# RelayBoard.net
KiCad netlist of a schematic drawn in Altium Designer
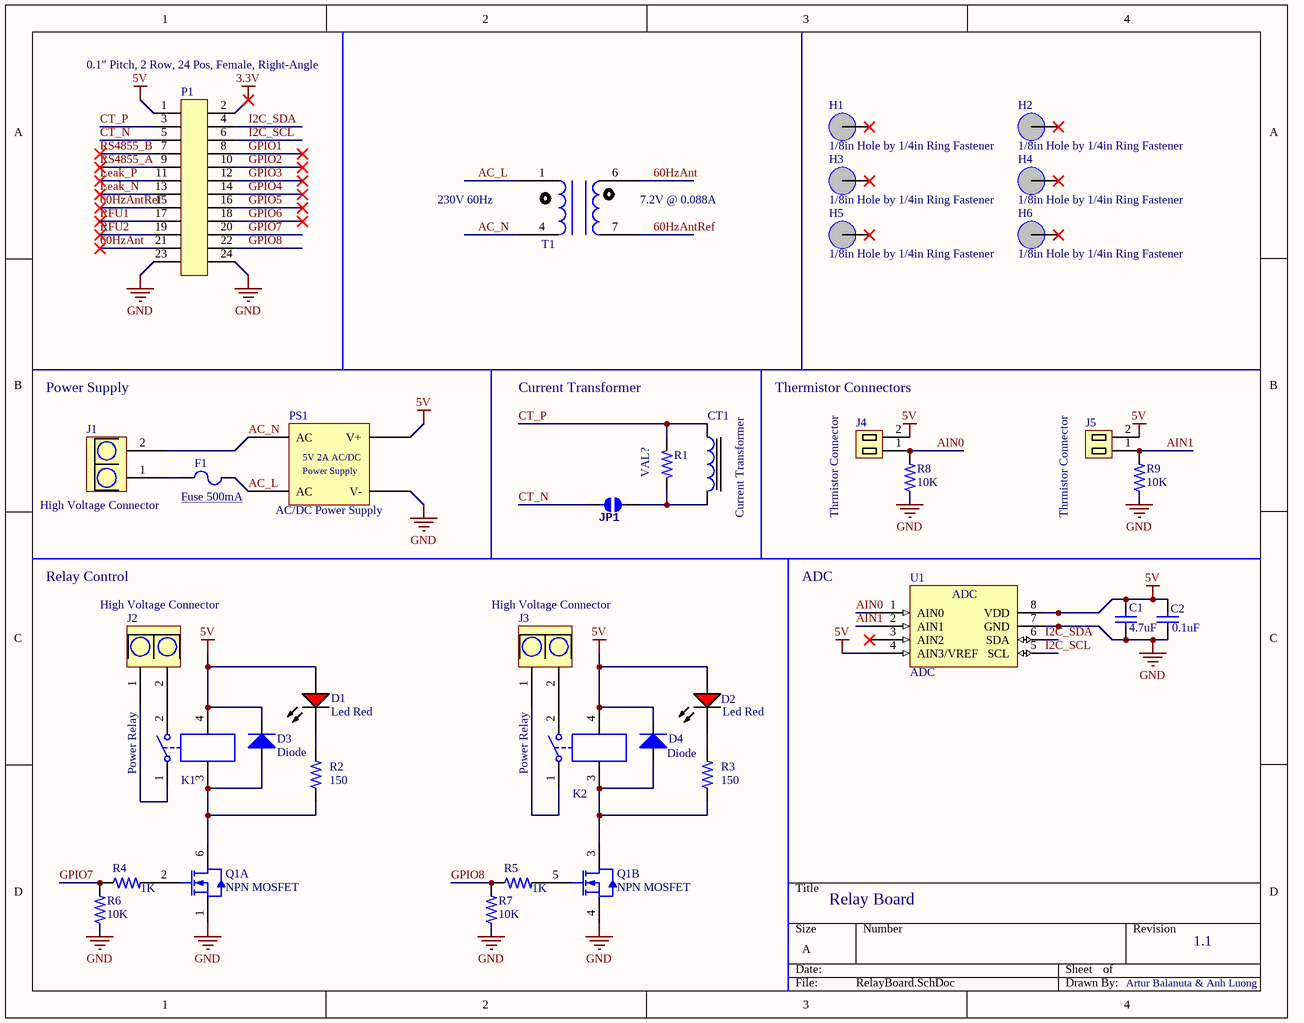
[diagram p0: RelayBoard.SchDoc]

(export (version "E")
  (design (tool "Eeschema 10.0.6"))
  (components
    (comp (ref "C1")
      (value "4.7uF")
      (footprint "CAPC1608X09L - CAP0603")
      (description "SMT 0603 Ceramic Capacitor")
      (fields (field (name "TOLERANCE") "10%") (field (name "VOLTAGE") "6.3V"))
      (libsource (lib "Passives") (part "CAP0603 4.7uF 10% 6.3V X7R"))
    )
    (comp (ref "C2")
      (value "0.1uF")
      (footprint "CAPC1608X09L - CAP0603")
      (description "SMT 0603 Ceramic Capacitor")
      (fields (field (name "TOLERANCE") "10%") (field (name "VOLTAGE") "25V"))
      (libsource (lib "Passives") (part "CAP0603 0.1uF 10% 25V X7R"))
    )
    (comp (ref "CT1")
      (value "Current Transformer")
      (footprint "CT-CR8348")
      (description "TRANSF CURRENT .27\" OPENING PCB 50A")
      (libsource (lib "Passives") (part "CT CR8348-2000"))
    )
    (comp (ref "D1")
      (value "Led Red")
      (footprint "LED-0603 .7MM TALL")
      (description "LED RED CLEAR 0603 SMD 250 mcd")
      (libsource (lib "Passives") (part "LED0603 RED 20mA 250mcd"))
    )
    (comp (ref "D2")
      (value "Led Red")
      (footprint "LED-0603 .7MM TALL")
      (description "LED RED CLEAR 0603 SMD 250 mcd")
      (libsource (lib "Passives") (part "LED0603 RED 20mA 250mcd"))
    )
    (comp (ref "D3")
      (value "Diode")
      (footprint "SOD-80  MiniMELF")
      (description "DIODE GEN 50V 600MA MINI MELF")
      (libsource (lib "Passives") (part "Diode LL4150GS18"))
    )
    (comp (ref "D4")
      (value "Diode")
      (footprint "SOD-80  MiniMELF")
      (description "DIODE GEN 50V 600MA MINI MELF")
      (libsource (lib "Passives") (part "Diode LL4150GS18"))
    )
    (comp (ref "F1")
      (value "Fuse 500mA")
      (footprint "FUSE M10742X40L Schurter UMK 250 Series")
      (description "FUSE UMK 250 FUSE WITH HOLDER 500MA F")
      (libsource (lib "Passives") (part "FUSE-Schurter-3404.2463.22"))
    )
    (comp (ref "H1")
      (value "1/8in Hole by 1/4in Ring Fastener")
      (footprint "1/8in Fastener Hole")
      (libsource (lib "Misc") (part "1/8in by 1/4in Fastner Hole"))
    )
    (comp (ref "H2")
      (value "1/8in Hole by 1/4in Ring Fastener")
      (footprint "1/8in Fastener Hole")
      (libsource (lib "Misc") (part "1/8in by 1/4in Fastner Hole"))
    )
    (comp (ref "H3")
      (value "1/8in Hole by 1/4in Ring Fastener")
      (footprint "1/8in Fastener Hole")
      (libsource (lib "Misc") (part "1/8in by 1/4in Fastner Hole"))
    )
    (comp (ref "H4")
      (value "1/8in Hole by 1/4in Ring Fastener")
      (footprint "1/8in Fastener Hole")
      (libsource (lib "Misc") (part "1/8in by 1/4in Fastner Hole"))
    )
    (comp (ref "H5")
      (value "1/8in Hole by 1/4in Ring Fastener")
      (footprint "1/8in Fastener Hole")
      (libsource (lib "Misc") (part "1/8in by 1/4in Fastner Hole"))
    )
    (comp (ref "H6")
      (value "1/8in Hole by 1/4in Ring Fastener")
      (footprint "1/8in Fastener Hole")
      (libsource (lib "Misc") (part "1/8in by 1/4in Fastner Hole"))
    )
    (comp (ref "J1")
      (value "High Voltage Connector")
      (footprint "2POS Barrier Block Terminal")
      (description "MOLEX  0386608802")
      (libsource (lib "Connectors") (part "2POS CONN BARRIER STRIP 2CIRC 0.5{dblquote} 45A 600V"))
    )
    (comp (ref "J2")
      (value "High Voltage Connector")
      (footprint "2POS Barrier Block Terminal")
      (description "MOLEX  0386608802")
      (libsource (lib "") (part "2POS CONN BARRIER STRIP 2CIRC 0.5{dblquote} 45A 600V_1"))
    )
    (comp (ref "J3")
      (value "High Voltage Connector")
      (footprint "2POS Barrier Block Terminal")
      (description "MOLEX  0386608802")
      (libsource (lib "") (part "2POS CONN BARRIER STRIP 2CIRC 0.5{dblquote} 45A 600V_1"))
    )
    (comp (ref "J4")
      (value "Thrmistor Connector")
      (footprint "2POS JST B02P-VL")
      (description "JST B02P-VL CONN HEADER 2POS VL SERIES TIN")
      (libsource (lib "Connectors") (part "2POS Thermistor Connector B02P-VL"))
    )
    (comp (ref "J5")
      (value "Thrmistor Connector")
      (footprint "2POS JST B02P-VL")
      (description "JST B02P-VL CONN HEADER 2POS VL SERIES TIN")
      (libsource (lib "Connectors") (part "2POS Thermistor Connector B02P-VL"))
    )
    (comp (ref "JP1")
      (value "JUMPER-PAD-2-NO")
      (footprint "PAD-JUMPER-2-NO_NO_SILK")
      (libsource (lib "Passives") (part "JUMPER-PAD-2-NO"))
    )
    (comp (ref "K1")
      (value "Power Relay")
      (footprint "T9AS1D12-5")
      (description "Single-Pole Single-Throw Relay")
      (fields (field (name "PART NUMBER") "T9AS1D12-5"))
      (libsource (lib "Relays") (part "T9AS1D12-5"))
    )
    (comp (ref "K2")
      (value "Power Relay")
      (footprint "T9AS1D12-5")
      (description "Single-Pole Single-Throw Relay")
      (fields (field (name "PART NUMBER") "T9AS1D12-5"))
      (libsource (lib "Relays") (part "T9AS1D12-5"))
    )
    (comp (ref "P1")
      (value "0.1\" Pitch, 2 Row, 24 Pos, Female, Right-Angle")
      (footprint "0.1 inch 2 row 24 pos female right-angle header Sullins")
      (description "Sullins 0.1\" 2 row 24 position female right-angle header")
      (libsource (lib "Connectors") (part "0.1{dblquote} 2 row 24 position female right-angle header sullins"))
    )
    (comp (ref "PS1")
      (value "AC/DC Power Supply")
      (footprint "IRM-10-5")
      (description "AC/DC Power Modules 5V 2A 10W 85-264Vin Encap PS")
      (libsource (lib "Power") (part "IRM-10-5"))
    )
    (comp (ref "Q1")
      (value "NPN MOSFET")
      (footprint "SC-70-6  (SOT-363)")
      (description "2N-CH NPN MOSFET 20V 1.3A SOT-363")
      (libsource (lib "Actives") (part "SI1922EDH-T1-GE3CT"))
    )
    (comp (ref "R1")
      (value "VAL?")
      (footprint "RESC1608X06L - RES0603")
      (description "SMT 0603 Ceramic Resistor")
      (libsource (lib "Passives") (part "RES0603"))
    )
    (comp (ref "R2")
      (value "150")
      (footprint "RESC1608X06L - RES0603")
      (description "SMT 0603 Ceramic Resistor")
      (libsource (lib "Passives") (part "RES0603 150 1% 1/10W_1"))
    )
    (comp (ref "R3")
      (value "150")
      (footprint "RESC1608X06L - RES0603")
      (description "SMT 0603 Ceramic Resistor")
      (libsource (lib "Passives") (part "RES0603 150 1% 1/10W_1"))
    )
    (comp (ref "R4")
      (value "1K")
      (footprint "RESC1608X06L - RES0603")
      (description "SMT 0603 Ceramic Resistor")
      (fields (field (name "POWER") "1/10W") (field (name "TOLERANCE") "1%"))
      (libsource (lib "Passives") (part "RES0603 1K 1% 1/10W"))
    )
    (comp (ref "R5")
      (value "1K")
      (footprint "RESC1608X06L - RES0603")
      (description "SMT 0603 Ceramic Resistor")
      (fields (field (name "POWER") "1/10W") (field (name "TOLERANCE") "1%"))
      (libsource (lib "Passives") (part "RES0603 1K 1% 1/10W"))
    )
    (comp (ref "R6")
      (value "10K")
      (footprint "RESC1608X06L - RES0603")
      (description "SMT 0603 Ceramic Resistor")
      (fields (field (name "POWER") "1/10W") (field (name "TOLERANCE") "1%"))
      (libsource (lib "Passives") (part "RES0603 10K 1% 1/10W"))
    )
    (comp (ref "R7")
      (value "10K")
      (footprint "RESC1608X06L - RES0603")
      (description "SMT 0603 Ceramic Resistor")
      (fields (field (name "POWER") "1/10W") (field (name "TOLERANCE") "1%"))
      (libsource (lib "Passives") (part "RES0603 10K 1% 1/10W"))
    )
    (comp (ref "R8")
      (value "10K")
      (footprint "RESC1608X06L - RES0603")
      (description "SMT 0603 Ceramic Resistor")
      (fields (field (name "POWER") "1/10W") (field (name "TOLERANCE") "1%"))
      (libsource (lib "Passives") (part "RES0603 10K 1% 1/10W"))
    )
    (comp (ref "R9")
      (value "10K")
      (footprint "RESC1608X06L - RES0603")
      (description "SMT 0603 Ceramic Resistor")
      (fields (field (name "POWER") "1/10W") (field (name "TOLERANCE") "1%"))
      (libsource (lib "Passives") (part "RES0603 10K 1% 1/10W"))
    )
    (comp (ref "T1")
      (value "SPK00304")
      (footprint "SPK003")
      (description "Standard PCB-Transformers ¦ SPK-003 ¦ POWER 0.35 VA")
      (libsource (lib "Power") (part "SPK00304"))
    )
    (comp (ref "U1")
      (value "ADC")
      (footprint "8L uMAX/uSOP TSOP65P490X110-8L")
      (description "IC ADC I2C/SRL 12BIT 4CH 8UMAX")
      (libsource (lib "Actives") (part "MAX11612EUA+"))
    )
  )
  (nets
    (net (code "1") (name "/60HzAnt") (class "Default")
      (node (ref "P1") (pin "21") (pintype "passive"))
      (node (ref "T1") (pin "6") (pinfunction "6_6") (pintype "passive"))
    )
    (net (code "2") (name "/60HzAntRef") (class "Default")
      (node (ref "P1") (pin "15") (pintype "passive"))
      (node (ref "T1") (pin "7") (pinfunction "7_7") (pintype "passive"))
    )
    (net (code "3") (name "/AC_L") (class "Default")
      (node (ref "F1") (pin "2") (pinfunction "2_2") (pintype "passive"))
      (node (ref "PS1") (pin "AC1") (pinfunction "AC_AC1") (pintype "power_in"))
      (node (ref "T1") (pin "1") (pinfunction "1_1") (pintype "passive"))
    )
    (net (code "4") (name "/AC_N") (class "Default")
      (node (ref "J1") (pin "2") (pinfunction "2_2") (pintype "power_in"))
      (node (ref "PS1") (pin "AC2") (pinfunction "AC_AC2") (pintype "power_in"))
      (node (ref "T1") (pin "4") (pinfunction "4_4") (pintype "passive"))
    )
    (net (code "5") (name "/AIN0") (class "Default")
      (node (ref "J4") (pin "1") (pinfunction "1_1") (pintype "passive"))
      (node (ref "R8") (pin "2") (pinfunction "2_2") (pintype "passive"))
      (node (ref "U1") (pin "1") (pinfunction "AIN0_1") (pintype "input"))
    )
    (net (code "6") (name "/AIN1") (class "Default")
      (node (ref "J5") (pin "1") (pinfunction "1_1") (pintype "passive"))
      (node (ref "R9") (pin "2") (pinfunction "2_2") (pintype "passive"))
      (node (ref "U1") (pin "2") (pinfunction "AIN1_2") (pintype "input"))
    )
    (net (code "7") (name "/CT_N") (class "Default")
      (node (ref "JP1") (pin "1") (pinfunction "1_1") (pintype "passive"))
      (node (ref "P1") (pin "5") (pintype "passive"))
    )
    (net (code "8") (name "/CT_P") (class "Default")
      (node (ref "CT1") (pin "1") (pinfunction "1_1") (pintype "passive"))
      (node (ref "P1") (pin "3") (pintype "passive"))
      (node (ref "R1") (pin "2") (pinfunction "2_2") (pintype "passive"))
    )
    (net (code "9") (name "/GPIO1") (class "Default")
      (node (ref "P1") (pin "8") (pintype "passive+no_connect"))
    )
    (net (code "10") (name "/GPIO2") (class "Default")
      (node (ref "P1") (pin "10") (pintype "passive+no_connect"))
    )
    (net (code "11") (name "/GPIO3") (class "Default")
      (node (ref "P1") (pin "12") (pintype "passive+no_connect"))
    )
    (net (code "12") (name "/GPIO4") (class "Default")
      (node (ref "P1") (pin "14") (pintype "passive+no_connect"))
    )
    (net (code "13") (name "/GPIO5") (class "Default")
      (node (ref "P1") (pin "16") (pintype "passive+no_connect"))
    )
    (net (code "14") (name "/GPIO6") (class "Default")
      (node (ref "P1") (pin "18") (pintype "passive+no_connect"))
    )
    (net (code "15") (name "/GPIO7") (class "Default")
      (node (ref "P1") (pin "20") (pintype "passive"))
      (node (ref "R4") (pin "1") (pinfunction "1_1") (pintype "passive"))
      (node (ref "R6") (pin "2") (pinfunction "2_2") (pintype "passive"))
    )
    (net (code "16") (name "/GPIO8") (class "Default")
      (node (ref "P1") (pin "22") (pintype "passive"))
      (node (ref "R5") (pin "1") (pinfunction "1_1") (pintype "passive"))
      (node (ref "R7") (pin "2") (pinfunction "2_2") (pintype "passive"))
    )
    (net (code "17") (name "/I2C_SCL") (class "Default")
      (node (ref "P1") (pin "6") (pintype "passive"))
      (node (ref "U1") (pin "5") (pinfunction "SCL_5") (pintype "bidirectional"))
    )
    (net (code "18") (name "/I2C_SDA") (class "Default")
      (node (ref "P1") (pin "4") (pintype "passive"))
      (node (ref "U1") (pin "6") (pinfunction "SDA_6") (pintype "bidirectional"))
    )
    (net (code "19") (name "/Leak_N") (class "Default")
      (node (ref "P1") (pin "13") (pintype "passive+no_connect"))
    )
    (net (code "20") (name "/Leak_P") (class "Default")
      (node (ref "P1") (pin "11") (pintype "passive+no_connect"))
    )
    (net (code "21") (name "/RFU1") (class "Default")
      (node (ref "P1") (pin "17") (pintype "passive+no_connect"))
    )
    (net (code "22") (name "/RFU2") (class "Default")
      (node (ref "P1") (pin "19") (pintype "passive+no_connect"))
    )
    (net (code "23") (name "/RS4855_A") (class "Default")
      (node (ref "P1") (pin "9") (pintype "passive+no_connect"))
    )
    (net (code "24") (name "/RS4855_B") (class "Default")
      (node (ref "P1") (pin "7") (pintype "passive+no_connect"))
    )
    (net (code "25") (name "3.3V") (class "Default") (node (ref "P1") (pin "2") (pintype "passive")))
    (net (code "26") (name "5V") (class "Default")
      (node (ref "C1") (pin "2") (pinfunction "2_2") (pintype "passive"))
      (node (ref "C2") (pin "2") (pinfunction "2_2") (pintype "passive"))
      (node (ref "D1") (pin "A") (pinfunction "A_A") (pintype "passive"))
      (node (ref "D2") (pin "A") (pinfunction "A_A") (pintype "passive"))
      (node (ref "D3") (pin "1") (pinfunction "K_1") (pintype "passive"))
      (node (ref "D4") (pin "1") (pinfunction "K_1") (pintype "passive"))
      (node (ref "J4") (pin "2") (pinfunction "2_2") (pintype "passive"))
      (node (ref "J5") (pin "2") (pinfunction "2_2") (pintype "passive"))
      (node (ref "K1") (pin "4") (pinfunction "4_4") (pintype "passive"))
      (node (ref "K2") (pin "4") (pinfunction "4_4") (pintype "passive"))
      (node (ref "P1") (pin "1") (pintype "passive"))
      (node (ref "PS1") (pin "V+") (pinfunction "V+_V+") (pintype "power_in"))
      (node (ref "U1") (pin "4") (pinfunction "AIN3/VREF_4") (pintype "input"))
      (node (ref "U1") (pin "8") (pinfunction "VDD_8") (pintype "power_in"))
    )
    (net (code "27") (name "GND") (class "Default")
      (node (ref "C1") (pin "1") (pinfunction "1_1") (pintype "passive"))
      (node (ref "C2") (pin "1") (pinfunction "1_1") (pintype "passive"))
      (node (ref "P1") (pin "23") (pintype "passive"))
      (node (ref "P1") (pin "24") (pintype "passive"))
      (node (ref "PS1") (pin "V-") (pinfunction "V-_V-") (pintype "power_in"))
      (node (ref "Q1") (pin "1") (pinfunction "S1_1") (pintype "power_in"))
      (node (ref "Q1") (pin "4") (pinfunction "S2_4") (pintype "power_in"))
      (node (ref "R6") (pin "1") (pinfunction "1_1") (pintype "passive"))
      (node (ref "R7") (pin "1") (pinfunction "1_1") (pintype "passive"))
      (node (ref "R8") (pin "1") (pinfunction "1_1") (pintype "passive"))
      (node (ref "R9") (pin "1") (pinfunction "1_1") (pintype "passive"))
      (node (ref "U1") (pin "7") (pinfunction "GND_7") (pintype "power_in"))
    )
    (net (code "28") (name "Net-(CT1-Pad2)") (class "Default")
      (node (ref "CT1") (pin "2") (pinfunction "2_2") (pintype "passive"))
      (node (ref "JP1") (pin "2") (pinfunction "2_2") (pintype "passive"))
      (node (ref "R1") (pin "1") (pinfunction "1_1") (pintype "passive"))
    )
    (net (code "29") (name "Net-(D1-PadK)") (class "Default")
      (node (ref "D1") (pin "K") (pinfunction "K_K") (pintype "passive"))
      (node (ref "R2") (pin "2") (pinfunction "2_2") (pintype "passive"))
    )
    (net (code "30") (name "Net-(D2-PadK)") (class "Default")
      (node (ref "D2") (pin "K") (pinfunction "K_K") (pintype "passive"))
      (node (ref "R3") (pin "2") (pinfunction "2_2") (pintype "passive"))
    )
    (net (code "31") (name "Net-(D3-A)") (class "Default")
      (node (ref "D3") (pin "2") (pinfunction "A_2") (pintype "passive"))
      (node (ref "K1") (pin "3") (pinfunction "3_3") (pintype "passive"))
      (node (ref "Q1") (pin "6") (pinfunction "D1_6") (pintype "power_in"))
      (node (ref "R2") (pin "1") (pinfunction "1_1") (pintype "passive"))
    )
    (net (code "32") (name "Net-(D4-A)") (class "Default")
      (node (ref "D4") (pin "2") (pinfunction "A_2") (pintype "passive"))
      (node (ref "K2") (pin "3") (pinfunction "3_3") (pintype "passive"))
      (node (ref "Q1") (pin "3") (pinfunction "D2_3") (pintype "power_in"))
      (node (ref "R3") (pin "1") (pinfunction "1_1") (pintype "passive"))
    )
    (net (code "33") (name "Net-(F1-Pad1)") (class "Default")
      (node (ref "F1") (pin "1") (pinfunction "1_1") (pintype "passive"))
      (node (ref "J1") (pin "1") (pinfunction "1_1") (pintype "power_in"))
    )
    (net (code "34") (name "Net-(J2-Pad1)") (class "Default")
      (node (ref "J2") (pin "1") (pinfunction "1_1") (pintype "power_in"))
      (node (ref "K1") (pin "1") (pinfunction "1_1") (pintype "passive"))
    )
    (net (code "35") (name "Net-(J2-Pad2)") (class "Default")
      (node (ref "J2") (pin "2") (pinfunction "2_2") (pintype "power_in"))
      (node (ref "K1") (pin "2") (pinfunction "2_2") (pintype "passive"))
    )
    (net (code "36") (name "Net-(J3-Pad1)") (class "Default")
      (node (ref "J3") (pin "1") (pinfunction "1_1") (pintype "power_in"))
      (node (ref "K2") (pin "1") (pinfunction "1_1") (pintype "passive"))
    )
    (net (code "37") (name "Net-(J3-Pad2)") (class "Default")
      (node (ref "J3") (pin "2") (pinfunction "2_2") (pintype "power_in"))
      (node (ref "K2") (pin "2") (pinfunction "2_2") (pintype "passive"))
    )
    (net (code "38") (name "Net-(Q1A-G1)") (class "Default")
      (node (ref "Q1") (pin "2") (pinfunction "G1_2") (pintype "passive"))
      (node (ref "R4") (pin "2") (pinfunction "2_2") (pintype "passive"))
    )
    (net (code "39") (name "Net-(Q1B-G2)") (class "Default")
      (node (ref "Q1") (pin "5") (pinfunction "G2_5") (pintype "passive"))
      (node (ref "R5") (pin "2") (pinfunction "2_2") (pintype "passive"))
    )
    (net (code "40") (name "unconnected-(H1-Pad1)") (class "Default")
      (node (ref "H1") (pin "1") (pinfunction "1_1") (pintype "power_in+no_connect"))
    )
    (net (code "41") (name "unconnected-(H2-Pad1)") (class "Default")
      (node (ref "H2") (pin "1") (pinfunction "1_1") (pintype "power_in+no_connect"))
    )
    (net (code "42") (name "unconnected-(H3-Pad1)") (class "Default")
      (node (ref "H3") (pin "1") (pinfunction "1_1") (pintype "power_in+no_connect"))
    )
    (net (code "43") (name "unconnected-(H4-Pad1)") (class "Default")
      (node (ref "H4") (pin "1") (pinfunction "1_1") (pintype "power_in+no_connect"))
    )
    (net (code "44") (name "unconnected-(H5-Pad1)") (class "Default")
      (node (ref "H5") (pin "1") (pinfunction "1_1") (pintype "power_in+no_connect"))
    )
    (net (code "45") (name "unconnected-(H6-Pad1)") (class "Default")
      (node (ref "H6") (pin "1") (pinfunction "1_1") (pintype "power_in+no_connect"))
    )
    (net (code "46") (name "unconnected-(U1-AIN2-Pad3)") (class "Default")
      (node (ref "U1") (pin "3") (pinfunction "AIN2_3") (pintype "input+no_connect"))
    )
  )
)
